# Modulo_de_apertura_RS485.net
KiCad netlist of a schematic drawn in Altium Designer
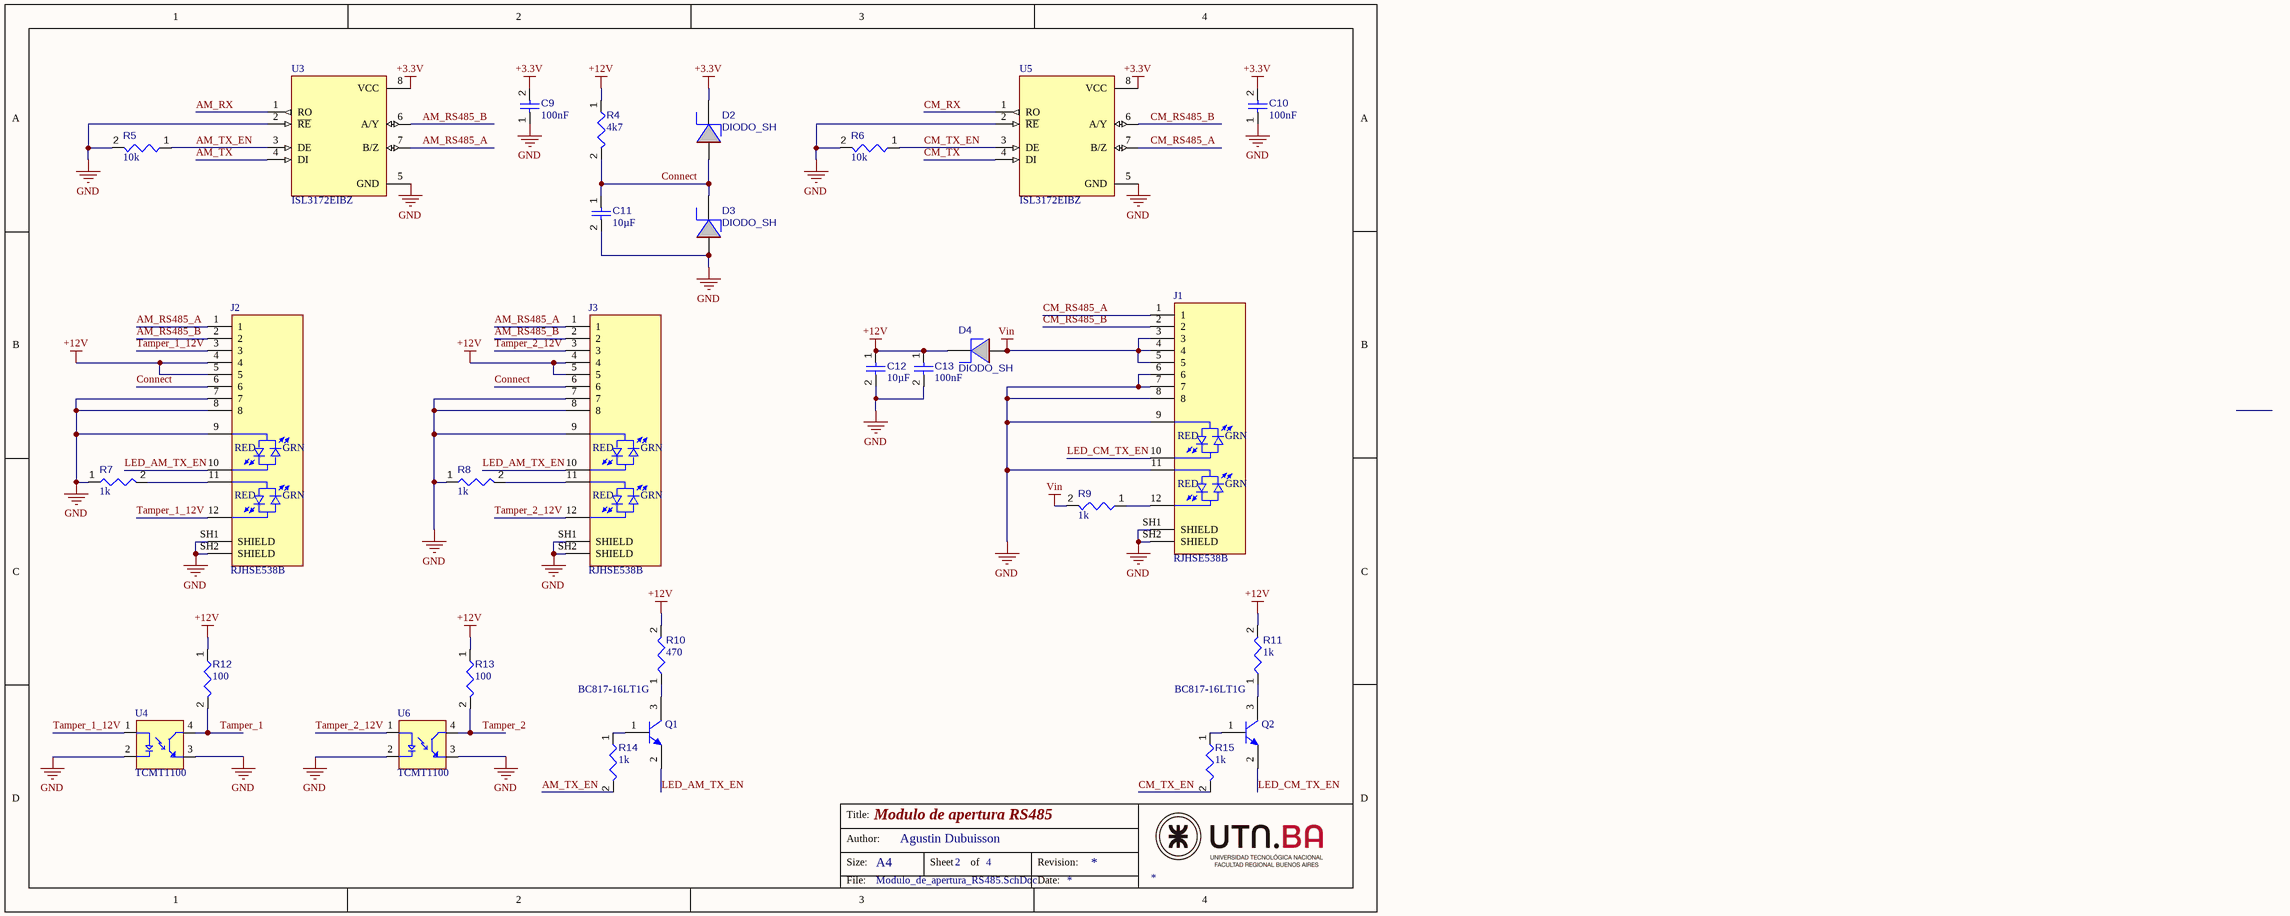
[diagram p0: Modulo_de_apertura_RS485.SchDoc]

(export (version "E")
  (design (tool "Eeschema 10.0.6"))
  (components
    (comp (ref "C9")
      (value "100nF")
      (footprint "CAPC0402(1005)60_L")
      (description "Chip Capacitor, 100nF +/-20%, 10V, 0402, Thickness 0.6 mm")
      (fields (field (name "TOLERANCE") "20%") (field (name "Comment") "Capacitor 100nF +/-20% 10V 0402"))
      (libsource (lib "Agustin Dubuisson") (part "CAP-NP-2"))
    )
    (comp (ref "C10")
      (value "100nF")
      (footprint "CAPC0402(1005)60_L")
      (description "Chip Capacitor, 100nF +/-20%, 10V, 0402, Thickness 0.6 mm")
      (fields (field (name "TOLERANCE") "20%") (field (name "Comment") "Capacitor 100nF +/-20% 10V 0402"))
      (libsource (lib "Agustin Dubuisson") (part "CAP-NP-2"))
    )
    (comp (ref "C11")
      (value "10µF")
      (footprint "CAPC0603(1608)100_L")
      (description "Chip Capacitor, 10µF +/-20%, 10V, 0603, Thickness 1 mm")
      (fields (field (name "TOLERANCE") "10%") (field (name "Comment") "Capacitor 10µF +/-20% 10V 0603"))
      (libsource (lib "Agustin Dubuisson") (part "CAP-NP-2"))
    )
    (comp (ref "C12")
      (value "10µF")
      (footprint "CAPC0603(1608)100_L")
      (description "Chip Capacitor, 10µF +/-20%, 10V, 0603, Thickness 1 mm")
      (fields (field (name "TOLERANCE") "10%") (field (name "Comment") "Capacitor 10µF +/-20% 10V 0603"))
      (libsource (lib "Agustin Dubuisson") (part "CAP-NP-2"))
    )
    (comp (ref "C13")
      (value "100nF")
      (footprint "CAPC0402(1005)60_L")
      (description "Chip Capacitor, 100nF +/-20%, 10V, 0402, Thickness 0.6 mm")
      (fields (field (name "TOLERANCE") "20%") (field (name "Comment") "Capacitor 100nF +/-20% 10V 0402"))
      (libsource (lib "Agustin Dubuisson") (part "CAP-NP-2"))
    )
    (comp (ref "D2")
      (value "DIODO_SH")
      (footprint "IDCI_WifiNode:D_SMA")
      (description "Diode Shottky")
      (libsource (lib "WifiNode") (part "DIODO_SH"))
    )
    (comp (ref "D3")
      (value "DIODO_SH")
      (footprint "IDCI_WifiNode:D_SMA")
      (description "Diode Shottky")
      (libsource (lib "WifiNode") (part "DIODO_SH"))
    )
    (comp (ref "D4")
      (value "DIODO_SH")
      (footprint "IDCI_WifiNode:D_SMA")
      (description "Diode Shottky")
      (libsource (lib "WifiNode") (part "DIODO_SH"))
    )
    (comp (ref "J1")
      (value "RJHSE538B")
      (footprint "AMPHENOL_RJHSE538B")
      (fields (field (name "MF") "{'manufacturer': u'Amphenol ICC (Commercial Products)'}"))
      (libsource (lib "RJHSE538B") (part "RJHSE538B"))
    )
    (comp (ref "J2")
      (value "RJHSE538B")
      (footprint "AMPHENOL_RJHSE538B")
      (fields (field (name "MF") "{'manufacturer': u'Amphenol ICC (Commercial Products)'}"))
      (libsource (lib "RJHSE538B") (part "RJHSE538B"))
    )
    (comp (ref "J3")
      (value "RJHSE538B")
      (footprint "AMPHENOL_RJHSE538B")
      (fields (field (name "MF") "{'manufacturer': u'Amphenol ICC (Commercial Products)'}"))
      (libsource (lib "RJHSE538B") (part "RJHSE538B"))
    )
    (comp (ref "Q1")
      (value "BC817-16LT1G")
      (footprint "ONSC-SOT-23-3-318-08_V")
      (description "General Purpose Transistor, NPN Silicon, 3-Pin SOT-23, Pb-Free, Tape and Reel")
      (fields (field (name "MANUFACTURER") "On Semiconductor"))
      (libsource (lib "Altium Content Vault") (part "ONSC-NPN-B1E2C3-3"))
    )
    (comp (ref "Q2")
      (value "BC817-16LT1G")
      (footprint "ONSC-SOT-23-3-318-08_V")
      (description "General Purpose Transistor, NPN Silicon, 3-Pin SOT-23, Pb-Free, Tape and Reel")
      (fields (field (name "MANUFACTURER") "On Semiconductor"))
      (libsource (lib "Altium Content Vault") (part "ONSC-NPN-B1E2C3-3"))
    )
    (comp (ref "R4")
      (value "4k7")
      (footprint "RESC0402(1005)_L")
      (description "Chip Resistor, 10 kOhms, +/-1 %, 63 mW, -55 to 125 degC, 0402")
      (fields (field (name "POWER") "63mW") (field (name "TOLERANCE") "1%"))
      (libsource (lib "Agustin Dubuisson") (part "RES-2"))
    )
    (comp (ref "R5")
      (value "10k")
      (footprint "RESC0402(1005)_L")
      (description "Chip Resistor, 10 kOhms, +/-1 %, 63 mW, -55 to 125 degC, 0402")
      (fields (field (name "POWER") "63mW") (field (name "TOLERANCE") "1%"))
      (libsource (lib "Agustin Dubuisson") (part "RES-2"))
    )
    (comp (ref "R6")
      (value "10k")
      (footprint "RESC0402(1005)_L")
      (description "Chip Resistor, 10 kOhms, +/-1 %, 63 mW, -55 to 125 degC, 0402")
      (fields (field (name "POWER") "63mW") (field (name "TOLERANCE") "1%"))
      (libsource (lib "Agustin Dubuisson") (part "RES-2"))
    )
    (comp (ref "R7")
      (value "1k")
      (footprint "RESC0402(1005)_L")
      (description "Chip Resistor, 10 kOhms, +/-1 %, 63 mW, -55 to 125 degC, 0402")
      (fields (field (name "POWER") "63mW") (field (name "TOLERANCE") "1%"))
      (libsource (lib "Agustin Dubuisson") (part "RES-2"))
    )
    (comp (ref "R8")
      (value "1k")
      (footprint "RESC0402(1005)_L")
      (description "Chip Resistor, 10 kOhms, +/-1 %, 63 mW, -55 to 125 degC, 0402")
      (fields (field (name "POWER") "63mW") (field (name "TOLERANCE") "1%"))
      (libsource (lib "Agustin Dubuisson") (part "RES-2"))
    )
    (comp (ref "R9")
      (value "1k")
      (footprint "RESC0402(1005)_L")
      (description "Chip Resistor, 10 kOhms, +/-1 %, 63 mW, -55 to 125 degC, 0402")
      (fields (field (name "POWER") "63mW") (field (name "TOLERANCE") "1%"))
      (libsource (lib "Agustin Dubuisson") (part "RES-2"))
    )
    (comp (ref "R10")
      (value "470")
      (footprint "RESC0402(1005)_L")
      (description "Chip Resistor, 10 kOhms, +/-1 %, 63 mW, -55 to 125 degC, 0402")
      (fields (field (name "POWER") "63mW") (field (name "TOLERANCE") "1%"))
      (libsource (lib "Agustin Dubuisson") (part "RES-2"))
    )
    (comp (ref "R11")
      (value "1k")
      (footprint "RESC0402(1005)_L")
      (description "Chip Resistor, 10 kOhms, +/-1 %, 63 mW, -55 to 125 degC, 0402")
      (fields (field (name "POWER") "63mW") (field (name "TOLERANCE") "1%"))
      (libsource (lib "Agustin Dubuisson") (part "RES-2"))
    )
    (comp (ref "R12")
      (value "100")
      (footprint "RESC0402(1005)_L")
      (description "Chip Resistor, 10 kOhms, +/-1 %, 63 mW, -55 to 125 degC, 0402")
      (fields (field (name "POWER") "63mW") (field (name "TOLERANCE") "1%"))
      (libsource (lib "Agustin Dubuisson") (part "RES-2"))
    )
    (comp (ref "R13")
      (value "100")
      (footprint "RESC0402(1005)_L")
      (description "Chip Resistor, 10 kOhms, +/-1 %, 63 mW, -55 to 125 degC, 0402")
      (fields (field (name "POWER") "63mW") (field (name "TOLERANCE") "1%"))
      (libsource (lib "Agustin Dubuisson") (part "RES-2"))
    )
    (comp (ref "R14")
      (value "1k")
      (footprint "RESC0402(1005)_L")
      (description "Chip Resistor, 10 kOhms, +/-1 %, 63 mW, -55 to 125 degC, 0402")
      (fields (field (name "POWER") "63mW") (field (name "TOLERANCE") "1%"))
      (libsource (lib "Agustin Dubuisson") (part "RES-2"))
    )
    (comp (ref "R15")
      (value "1k")
      (footprint "RESC0402(1005)_L")
      (description "Chip Resistor, 10 kOhms, +/-1 %, 63 mW, -55 to 125 degC, 0402")
      (fields (field (name "POWER") "63mW") (field (name "TOLERANCE") "1%"))
      (libsource (lib "Agustin Dubuisson") (part "RES-2"))
    )
    (comp (ref "U3")
      (value "ISL3172EIBZ")
      (footprint "SOIC127P600X175-8N")
      (description "1/1 Transceiver Half RS422, RS485 8-SOIC")
      (fields (field (name "MF") "Renesas Electronics America Inc"))
      (libsource (lib "ISL3172EIBZ") (part "ISL3172EIBZ"))
    )
    (comp (ref "U4")
      (value "TCMT1100")
      (footprint "SOIC127P700X230-4N")
      (description "Optoisolator Transistor Output 3750Vrms 1 Channel 4-SOP")
      (fields (field (name "MF") "Vishay Semiconductor"))
      (libsource (lib "TCMT1100") (part "TCMT1100"))
    )
    (comp (ref "U5")
      (value "ISL3172EIBZ")
      (footprint "SOIC127P600X175-8N")
      (description "1/1 Transceiver Half RS422, RS485 8-SOIC")
      (fields (field (name "MF") "Renesas Electronics America Inc"))
      (libsource (lib "ISL3172EIBZ") (part "ISL3172EIBZ"))
    )
    (comp (ref "U6")
      (value "TCMT1100")
      (footprint "SOIC127P700X230-4N")
      (description "Optoisolator Transistor Output 3750Vrms 1 Channel 4-SOP")
      (fields (field (name "MF") "Vishay Semiconductor"))
      (libsource (lib "TCMT1100") (part "TCMT1100"))
    )
  )
  (nets
    (net (code "1") (name "+3.3V") (class "Default")
      (node (ref "C10") (pin "2") (pinfunction "2_2") (pintype "passive"))
      (node (ref "C9") (pin "2") (pinfunction "2_2") (pintype "passive"))
      (node (ref "D2") (pin "2") (pinfunction "K_2") (pintype "passive"))
      (node (ref "U3") (pin "8") (pinfunction "VCC_8") (pintype "power_in"))
      (node (ref "U5") (pin "8") (pinfunction "VCC_8") (pintype "power_in"))
    )
    (net (code "2") (name "+12V") (class "Default")
      (node (ref "C12") (pin "1") (pinfunction "1_1") (pintype "passive"))
      (node (ref "C13") (pin "1") (pinfunction "1_1") (pintype "passive"))
      (node (ref "D4") (pin "2") (pinfunction "K_2") (pintype "passive"))
      (node (ref "J2") (pin "4") (pinfunction "4_4") (pintype "passive"))
      (node (ref "J2") (pin "5") (pinfunction "5_5") (pintype "passive"))
      (node (ref "J3") (pin "4") (pinfunction "4_4") (pintype "passive"))
      (node (ref "J3") (pin "5") (pinfunction "5_5") (pintype "passive"))
      (node (ref "R10") (pin "2") (pinfunction "2_2") (pintype "passive"))
      (node (ref "R11") (pin "2") (pinfunction "2_2") (pintype "passive"))
      (node (ref "R12") (pin "1") (pinfunction "1_1") (pintype "passive"))
      (node (ref "R13") (pin "1") (pinfunction "1_1") (pintype "passive"))
      (node (ref "R4") (pin "1") (pinfunction "1_1") (pintype "passive"))
    )
    (net (code "3") (name "/AM_RS485_A") (class "Default")
      (node (ref "J2") (pin "1") (pinfunction "1_1") (pintype "passive"))
      (node (ref "J3") (pin "1") (pinfunction "1_1") (pintype "passive"))
      (node (ref "U3") (pin "7") (pinfunction "B/Z_7") (pintype "bidirectional"))
    )
    (net (code "4") (name "/AM_RS485_B") (class "Default")
      (node (ref "J2") (pin "2") (pinfunction "2_2") (pintype "passive"))
      (node (ref "J3") (pin "2") (pinfunction "2_2") (pintype "passive"))
      (node (ref "U3") (pin "6") (pinfunction "A/Y_6") (pintype "bidirectional"))
    )
    (net (code "5") (name "/AM_RX") (class "Default")
      (node (ref "U3") (pin "1") (pinfunction "RO_1") (pintype "output"))
    )
    (net (code "6") (name "/AM_TX") (class "Default")
      (node (ref "U3") (pin "4") (pinfunction "DI_4") (pintype "input"))
    )
    (net (code "7") (name "/AM_TX_EN") (class "Default")
      (node (ref "R14") (pin "2") (pinfunction "2_2") (pintype "passive"))
      (node (ref "R5") (pin "1") (pinfunction "1_1") (pintype "passive"))
      (node (ref "U3") (pin "3") (pinfunction "DE_3") (pintype "input"))
    )
    (net (code "8") (name "/CM_RS485_A") (class "Default")
      (node (ref "J1") (pin "1") (pinfunction "1_1") (pintype "passive"))
      (node (ref "U5") (pin "7") (pinfunction "B/Z_7") (pintype "bidirectional"))
    )
    (net (code "9") (name "/CM_RS485_B") (class "Default")
      (node (ref "J1") (pin "2") (pinfunction "2_2") (pintype "passive"))
      (node (ref "U5") (pin "6") (pinfunction "A/Y_6") (pintype "bidirectional"))
    )
    (net (code "10") (name "/CM_RX") (class "Default")
      (node (ref "U5") (pin "1") (pinfunction "RO_1") (pintype "output"))
    )
    (net (code "11") (name "/CM_TX") (class "Default")
      (node (ref "U5") (pin "4") (pinfunction "DI_4") (pintype "input"))
    )
    (net (code "12") (name "/CM_TX_EN") (class "Default")
      (node (ref "R15") (pin "2") (pinfunction "2_2") (pintype "passive"))
      (node (ref "R6") (pin "1") (pinfunction "1_1") (pintype "passive"))
      (node (ref "U5") (pin "3") (pinfunction "DE_3") (pintype "input"))
    )
    (net (code "13") (name "/Connect") (class "Default")
      (node (ref "C11") (pin "1") (pinfunction "1_1") (pintype "passive"))
      (node (ref "D2") (pin "1") (pinfunction "A_1") (pintype "passive"))
      (node (ref "D3") (pin "2") (pinfunction "K_2") (pintype "passive"))
      (node (ref "J2") (pin "6") (pinfunction "6_6") (pintype "passive"))
      (node (ref "J3") (pin "6") (pinfunction "6_6") (pintype "passive"))
      (node (ref "R4") (pin "2") (pinfunction "2_2") (pintype "passive"))
    )
    (net (code "14") (name "/LED_AM_TX_EN") (class "Default")
      (node (ref "J2") (pin "10") (pinfunction "10_10") (pintype "passive"))
      (node (ref "J3") (pin "10") (pinfunction "10_10") (pintype "passive"))
      (node (ref "Q1") (pin "2") (pinfunction "E_2") (pintype "passive"))
    )
    (net (code "15") (name "/LED_CM_TX_EN") (class "Default")
      (node (ref "J1") (pin "10") (pinfunction "10_10") (pintype "passive"))
      (node (ref "Q2") (pin "2") (pinfunction "E_2") (pintype "passive"))
    )
    (net (code "16") (name "/Tamper_1") (class "Default")
      (node (ref "R12") (pin "2") (pinfunction "2_2") (pintype "passive"))
      (node (ref "U4") (pin "4") (pinfunction "CT_4") (pintype "passive"))
    )
    (net (code "17") (name "/Tamper_1_12V") (class "Default")
      (node (ref "J2") (pin "12") (pinfunction "12_12") (pintype "passive"))
      (node (ref "J2") (pin "3") (pinfunction "3_3") (pintype "passive"))
      (node (ref "U4") (pin "1") (pinfunction "A_1") (pintype "passive"))
    )
    (net (code "18") (name "/Tamper_2") (class "Default")
      (node (ref "R13") (pin "2") (pinfunction "2_2") (pintype "passive"))
      (node (ref "U6") (pin "4") (pinfunction "CT_4") (pintype "passive"))
    )
    (net (code "19") (name "/Tamper_2_12V") (class "Default")
      (node (ref "J3") (pin "12") (pinfunction "12_12") (pintype "passive"))
      (node (ref "J3") (pin "3") (pinfunction "3_3") (pintype "passive"))
      (node (ref "U6") (pin "1") (pinfunction "A_1") (pintype "passive"))
    )
    (net (code "20") (name "GND") (class "Default")
      (node (ref "C10") (pin "1") (pinfunction "1_1") (pintype "passive"))
      (node (ref "C11") (pin "2") (pinfunction "2_2") (pintype "passive"))
      (node (ref "C12") (pin "2") (pinfunction "2_2") (pintype "passive"))
      (node (ref "C13") (pin "2") (pinfunction "2_2") (pintype "passive"))
      (node (ref "C9") (pin "1") (pinfunction "1_1") (pintype "passive"))
      (node (ref "D3") (pin "1") (pinfunction "A_1") (pintype "passive"))
      (node (ref "J1") (pin "11") (pinfunction "11_11") (pintype "passive"))
      (node (ref "J1") (pin "6") (pinfunction "6_6") (pintype "passive"))
      (node (ref "J1") (pin "7") (pinfunction "7_7") (pintype "passive"))
      (node (ref "J1") (pin "8") (pinfunction "8_8") (pintype "passive"))
      (node (ref "J1") (pin "9") (pinfunction "9_9") (pintype "passive"))
      (node (ref "J1") (pin "SH1") (pinfunction "SHIELD_SH1") (pintype "passive"))
      (node (ref "J1") (pin "SH2") (pinfunction "SHIELD_SH2") (pintype "passive"))
      (node (ref "J2") (pin "7") (pinfunction "7_7") (pintype "passive"))
      (node (ref "J2") (pin "8") (pinfunction "8_8") (pintype "passive"))
      (node (ref "J2") (pin "9") (pinfunction "9_9") (pintype "passive"))
      (node (ref "J2") (pin "SH1") (pinfunction "SHIELD_SH1") (pintype "passive"))
      (node (ref "J2") (pin "SH2") (pinfunction "SHIELD_SH2") (pintype "passive"))
      (node (ref "J3") (pin "7") (pinfunction "7_7") (pintype "passive"))
      (node (ref "J3") (pin "8") (pinfunction "8_8") (pintype "passive"))
      (node (ref "J3") (pin "9") (pinfunction "9_9") (pintype "passive"))
      (node (ref "J3") (pin "SH1") (pinfunction "SHIELD_SH1") (pintype "passive"))
      (node (ref "J3") (pin "SH2") (pinfunction "SHIELD_SH2") (pintype "passive"))
      (node (ref "R5") (pin "2") (pinfunction "2_2") (pintype "passive"))
      (node (ref "R6") (pin "2") (pinfunction "2_2") (pintype "passive"))
      (node (ref "R7") (pin "1") (pinfunction "1_1") (pintype "passive"))
      (node (ref "R8") (pin "1") (pinfunction "1_1") (pintype "passive"))
      (node (ref "U3") (pin "2") (pinfunction "~{RE}_2") (pintype "input"))
      (node (ref "U3") (pin "5") (pinfunction "GND_5") (pintype "power_in"))
      (node (ref "U4") (pin "2") (pinfunction "C_2") (pintype "passive"))
      (node (ref "U4") (pin "3") (pinfunction "ET_3") (pintype "passive"))
      (node (ref "U5") (pin "2") (pinfunction "~{RE}_2") (pintype "input"))
      (node (ref "U5") (pin "5") (pinfunction "GND_5") (pintype "power_in"))
      (node (ref "U6") (pin "2") (pinfunction "C_2") (pintype "passive"))
      (node (ref "U6") (pin "3") (pinfunction "ET_3") (pintype "passive"))
    )
    (net (code "21") (name "Net-(J1-Pad12)") (class "Default")
      (node (ref "J1") (pin "12") (pinfunction "12_12") (pintype "passive"))
      (node (ref "R9") (pin "1") (pinfunction "1_1") (pintype "passive"))
    )
    (net (code "22") (name "Net-(J2-Pad11)") (class "Default")
      (node (ref "J2") (pin "11") (pinfunction "11_11") (pintype "passive"))
      (node (ref "R7") (pin "2") (pinfunction "2_2") (pintype "passive"))
    )
    (net (code "23") (name "Net-(J3-Pad11)") (class "Default")
      (node (ref "J3") (pin "11") (pinfunction "11_11") (pintype "passive"))
      (node (ref "R8") (pin "2") (pinfunction "2_2") (pintype "passive"))
    )
    (net (code "24") (name "Net-(Q1-B)") (class "Default")
      (node (ref "Q1") (pin "1") (pinfunction "B_1") (pintype "passive"))
      (node (ref "R14") (pin "1") (pinfunction "1_1") (pintype "passive"))
    )
    (net (code "25") (name "Net-(Q1-C)") (class "Default")
      (node (ref "Q1") (pin "3") (pinfunction "C_3") (pintype "passive"))
      (node (ref "R10") (pin "1") (pinfunction "1_1") (pintype "passive"))
    )
    (net (code "26") (name "Net-(Q2-B)") (class "Default")
      (node (ref "Q2") (pin "1") (pinfunction "B_1") (pintype "passive"))
      (node (ref "R15") (pin "1") (pinfunction "1_1") (pintype "passive"))
    )
    (net (code "27") (name "Net-(Q2-C)") (class "Default")
      (node (ref "Q2") (pin "3") (pinfunction "C_3") (pintype "passive"))
      (node (ref "R11") (pin "1") (pinfunction "1_1") (pintype "passive"))
    )
    (net (code "28") (name "Vin") (class "Default")
      (node (ref "D4") (pin "1") (pinfunction "A_1") (pintype "passive"))
      (node (ref "J1") (pin "3") (pinfunction "3_3") (pintype "passive"))
      (node (ref "J1") (pin "4") (pinfunction "4_4") (pintype "passive"))
      (node (ref "J1") (pin "5") (pinfunction "5_5") (pintype "passive"))
      (node (ref "R9") (pin "2") (pinfunction "2_2") (pintype "passive"))
    )
  )
)
